# LTE.net
KiCad netlist of a schematic drawn in Altium Designer
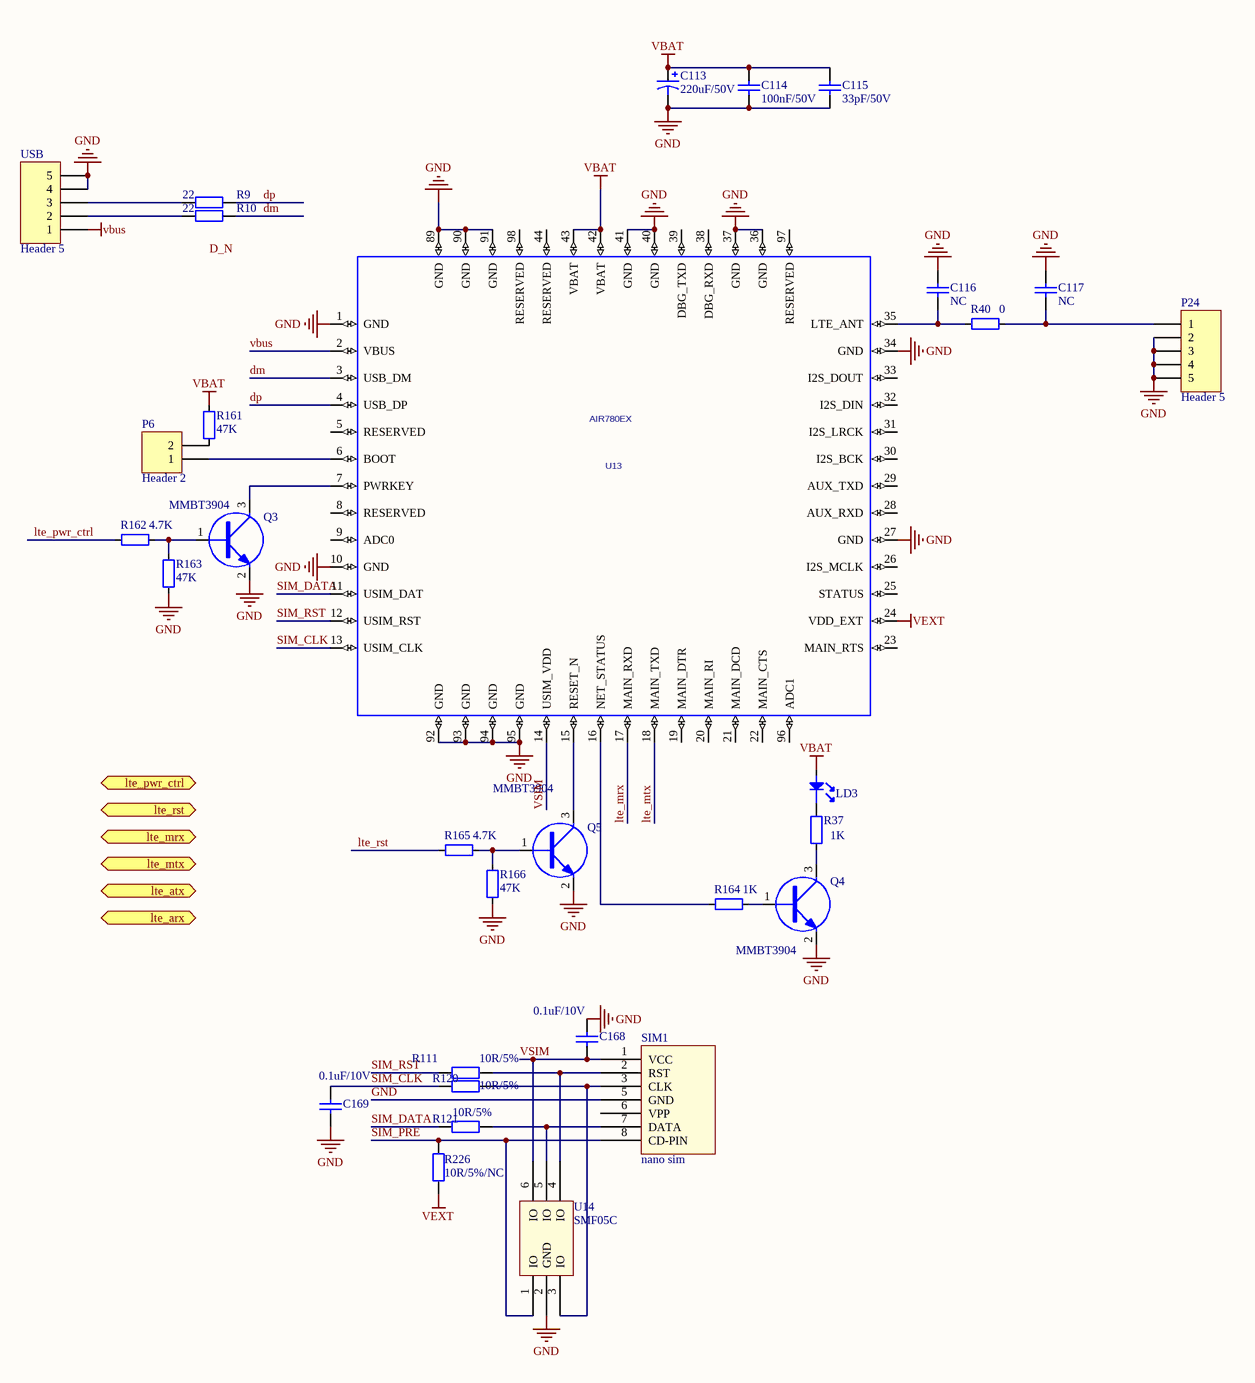
[diagram p0: LTE.SchDoc]

(export (version "E")
  (design (tool "Eeschema 10.0.6"))
  (components
    (comp (ref "C113")
      (value "220uF/50V")
      (footprint "Φ10×10")
      (description "Polarized Capacitor (Radial)")
      (fields (field (name "PUBLISHER") "Altium Limited"))
      (libsource (lib "Miscellaneous Devices") (part "Cap Pol1"))
    )
    (comp (ref "C114")
      (value "100nF/50V")
      (footprint "0603C")
      (description "Capacitor")
      (fields (field (name "PUBLISHER") "Altium Limited"))
      (libsource (lib "Miscellaneous Devices") (part "Cap"))
    )
    (comp (ref "C115")
      (value "33pF/50V")
      (footprint "0603C")
      (description "Capacitor")
      (fields (field (name "PUBLISHER") "Altium Limited"))
      (libsource (lib "Miscellaneous Devices") (part "Cap"))
    )
    (comp (ref "C116")
      (value "NC")
      (footprint "0603c")
      (description "Capacitor")
      (fields (field (name "PUBLISHER") "Altium Limited"))
      (libsource (lib "Miscellaneous Devices") (part "Cap"))
    )
    (comp (ref "C117")
      (value "NC")
      (footprint "0603c")
      (description "Capacitor")
      (fields (field (name "PUBLISHER") "Altium Limited"))
      (libsource (lib "Miscellaneous Devices") (part "Cap"))
    )
    (comp (ref "C168")
      (value "0.1uF/10V")
      (footprint "0603c")
      (description "Capacitor")
      (fields (field (name "PUBLISHER") "Altium Limited"))
      (libsource (lib "Miscellaneous Devices") (part "Cap"))
    )
    (comp (ref "C169")
      (value "0.1uF/10V")
      (footprint "0603c")
      (description "Capacitor")
      (fields (field (name "PUBLISHER") "Altium Limited"))
      (libsource (lib "Miscellaneous Devices") (part "Cap"))
    )
    (comp (ref "LD3")
      (value "LED_Green_19-217")
      (footprint "0603led")
      (libsource (lib "RC_M_D_00") (part "LED_Green_19-217"))
    )
    (comp (ref "P6")
      (value "Header 2")
      (footprint "HDR1X2")
      (description "Header, 2-Pin")
      (fields (field (name "PUBLISHER") "Altium Limited"))
      (libsource (lib "Miscellaneous Connectors") (part "Header 2"))
    )
    (comp (ref "P24")
      (value "Header 5")
      (footprint "KH-SMA-KE-Z")
      (description "Header, 5-Pin")
      (fields (field (name "PUBLISHER") "Altium Limited"))
      (libsource (lib "Miscellaneous Connectors") (part "Header 5"))
    )
    (comp (ref "Q3")
      (value "MMBT3904")
      (footprint "SOT23-3")
      (libsource (lib "CenLib") (part "NPN_MMBT3904"))
    )
    (comp (ref "Q4")
      (value "MMBT3904")
      (footprint "SOT23-3")
      (libsource (lib "CenLib") (part "NPN_MMBT3904"))
    )
    (comp (ref "Q5")
      (value "MMBT3904")
      (footprint "SOT23-3")
      (libsource (lib "CenLib") (part "NPN_MMBT3904"))
    )
    (comp (ref "R9")
      (value "22")
      (footprint "0402R")
      (description "Resistor SMD - IEC symbol version")
      (libsource (lib "SX1276_e266v02a") (part "Resistor"))
    )
    (comp (ref "R10")
      (value "22")
      (footprint "0402R")
      (description "Resistor SMD - IEC symbol version")
      (libsource (lib "SX1276_e266v02a") (part "Resistor"))
    )
    (comp (ref "R37") (value "1K") (footprint "0603R") (libsource (lib "RC_M_D_00") (part "RES0603")))
    (comp (ref "R40") (value "0") (footprint "0603r") (libsource (lib "RC_M_D_00") (part "RES0603")))
    (comp (ref "R111")
      (value "10R/5%")
      (footprint "0603r")
      (description "Resistor")
      (fields (field (name "PUBLISHER") "Altium Limited"))
      (libsource (lib "") (part "Res2_1"))
    )
    (comp (ref "R120")
      (value "10R/5%")
      (footprint "0603r")
      (description "Resistor")
      (fields (field (name "PUBLISHER") "Altium Limited"))
      (libsource (lib "") (part "Res2_1"))
    )
    (comp (ref "R121")
      (value "10R/5%")
      (footprint "0603r")
      (description "Resistor")
      (fields (field (name "PUBLISHER") "Altium Limited"))
      (libsource (lib "") (part "Res2_1"))
    )
    (comp (ref "R161") (value "47K") (footprint "0603r") (libsource (lib "RC_M_D_00") (part "RES0603")))
    (comp (ref "R162") (value "4.7K") (footprint "0603R") (libsource (lib "RC_M_D_00") (part "RES0603")))
    (comp (ref "R163") (value "47K") (footprint "0603r") (libsource (lib "RC_M_D_00") (part "RES0603")))
    (comp (ref "R164") (value "1K") (footprint "0603r") (libsource (lib "RC_M_D_00") (part "RES0603")))
    (comp (ref "R165") (value "4.7K") (footprint "0603R") (libsource (lib "RC_M_D_00") (part "RES0603")))
    (comp (ref "R166") (value "47K") (footprint "0603r") (libsource (lib "RC_M_D_00") (part "RES0603")))
    (comp (ref "R226")
      (value "10R/5%/NC")
      (footprint "0603r")
      (description "Resistor")
      (fields (field (name "PUBLISHER") "Altium Limited"))
      (libsource (lib "Miscellaneous Devices") (part "Res2"))
    )
    (comp (ref "SIM1") (value "nano sim") (footprint "Nano SIM") (libsource (lib "lm") (part "nano sim")))
    (comp (ref "U13")
      (value "AIR780EX")
      (footprint "Air780EX_AD:AIR780EX")
      (libsource (lib "*") (part "AIR780EX"))
    )
    (comp (ref "U14") (value "SMF05C") (footprint "sc70-6l") (libsource (lib "lm") (part "SMF05C")))
    (comp (ref "USB")
      (value "Header 5")
      (footprint "USB-MICRO-5P")
      (description "Header, 5-Pin")
      (fields (field (name "PUBLISHER") "Altium Limited"))
      (libsource (lib "") (part "Header 5_1"))
    )
  )
  (nets
    (net (code "2") (name "/SIM_CLK") (class "Default")
      (node (ref "C169") (pin "1") (pinfunction "1_1") (pintype "passive"))
      (node (ref "R120") (pin "2") (pinfunction "2_2") (pintype "passive"))
      (node (ref "U13") (pin "13") (pinfunction "USIM_CLK_13") (pintype "bidirectional"))
    )
    (net (code "3") (name "/SIM_DATA") (class "Default")
      (node (ref "R121") (pin "2") (pinfunction "2_2") (pintype "passive"))
      (node (ref "U13") (pin "11") (pinfunction "USIM_DAT_11") (pintype "bidirectional"))
    )
    (net (code "4") (name "/SIM_PRE") (class "Default")
      (node (ref "R226") (pin "1") (pinfunction "1_1") (pintype "passive"))
      (node (ref "SIM1") (pin "8") (pinfunction "CD-PIN_8") (pintype "passive"))
      (node (ref "U14") (pin "1") (pinfunction "IO_1") (pintype "passive"))
    )
    (net (code "5") (name "/SIM_RST") (class "Default")
      (node (ref "R111") (pin "2") (pinfunction "2_2") (pintype "passive"))
      (node (ref "U13") (pin "12") (pinfunction "USIM_RST_12") (pintype "bidirectional"))
    )
    (net (code "6") (name "/VSIM") (class "Default")
      (node (ref "C168") (pin "2") (pinfunction "2_2") (pintype "passive"))
      (node (ref "SIM1") (pin "1") (pinfunction "VCC_1") (pintype "passive"))
      (node (ref "U13") (pin "14") (pinfunction "USIM_VDD_14") (pintype "bidirectional"))
      (node (ref "U14") (pin "6") (pinfunction "IO_6") (pintype "passive"))
    )
    (net (code "7") (name "/dm") (class "Default")
      (node (ref "R10") (pin "2") (pinfunction "2_2") (pintype "passive"))
      (node (ref "U13") (pin "3") (pinfunction "USB_DM_3") (pintype "bidirectional"))
    )
    (net (code "8") (name "/dp") (class "Default")
      (node (ref "R9") (pin "2") (pinfunction "2_2") (pintype "passive"))
      (node (ref "U13") (pin "4") (pinfunction "USB_DP_4") (pintype "bidirectional"))
    )
    (net (code "11") (name "/lte_mrx") (class "Default")
      (node (ref "U13") (pin "17") (pinfunction "MAIN_RXD_17") (pintype "bidirectional"))
    )
    (net (code "12") (name "/lte_mtx") (class "Default")
      (node (ref "U13") (pin "18") (pinfunction "MAIN_TXD_18") (pintype "bidirectional"))
    )
    (net (code "13") (name "/lte_pwr_ctrl") (class "Default")
      (node (ref "R162") (pin "1") (pinfunction "1_1") (pintype "passive"))
    )
    (net (code "14") (name "/lte_rst") (class "Default")
      (node (ref "R165") (pin "1") (pinfunction "1_1") (pintype "passive"))
    )
    (net (code "15") (name "GND") (class "Default")
      (node (ref "C113") (pin "2") (pinfunction "2_2") (pintype "passive"))
      (node (ref "C114") (pin "1") (pinfunction "1_1") (pintype "passive"))
      (node (ref "C115") (pin "1") (pinfunction "1_1") (pintype "passive"))
      (node (ref "C116") (pin "2") (pinfunction "2_2") (pintype "passive"))
      (node (ref "C117") (pin "2") (pinfunction "2_2") (pintype "passive"))
      (node (ref "C168") (pin "1") (pinfunction "1_1") (pintype "passive"))
      (node (ref "C169") (pin "2") (pinfunction "2_2") (pintype "passive"))
      (node (ref "P24") (pin "2") (pinfunction "2_2") (pintype "passive"))
      (node (ref "P24") (pin "3") (pinfunction "3_3") (pintype "passive"))
      (node (ref "P24") (pin "4") (pinfunction "4_4") (pintype "passive"))
      (node (ref "P24") (pin "5") (pinfunction "5_5") (pintype "passive"))
      (node (ref "Q3") (pin "2") (pinfunction "E_2") (pintype "passive"))
      (node (ref "Q4") (pin "2") (pinfunction "E_2") (pintype "passive"))
      (node (ref "Q5") (pin "2") (pinfunction "E_2") (pintype "passive"))
      (node (ref "R163") (pin "1") (pinfunction "1_1") (pintype "passive"))
      (node (ref "R166") (pin "1") (pinfunction "1_1") (pintype "passive"))
      (node (ref "SIM1") (pin "5") (pinfunction "GND_5") (pintype "passive"))
      (node (ref "U13") (pin "1") (pinfunction "GND_1") (pintype "bidirectional"))
      (node (ref "U13") (pin "10") (pinfunction "GND_10") (pintype "bidirectional"))
      (node (ref "U13") (pin "27") (pinfunction "GND_27") (pintype "bidirectional"))
      (node (ref "U13") (pin "34") (pinfunction "GND_34") (pintype "bidirectional"))
      (node (ref "U13") (pin "36") (pinfunction "GND_36") (pintype "bidirectional"))
      (node (ref "U13") (pin "37") (pinfunction "GND_37") (pintype "bidirectional"))
      (node (ref "U13") (pin "40") (pinfunction "GND_40") (pintype "bidirectional"))
      (node (ref "U13") (pin "41") (pinfunction "GND_41") (pintype "bidirectional"))
      (node (ref "U13") (pin "89") (pinfunction "GND_89") (pintype "bidirectional"))
      (node (ref "U13") (pin "90") (pinfunction "GND_90") (pintype "bidirectional"))
      (node (ref "U13") (pin "91") (pinfunction "GND_91") (pintype "bidirectional"))
      (node (ref "U13") (pin "92") (pinfunction "GND_92") (pintype "bidirectional"))
      (node (ref "U13") (pin "93") (pinfunction "GND_93") (pintype "bidirectional"))
      (node (ref "U13") (pin "94") (pinfunction "GND_94") (pintype "bidirectional"))
      (node (ref "U13") (pin "95") (pinfunction "GND_95") (pintype "bidirectional"))
      (node (ref "U14") (pin "2") (pinfunction "GND_2") (pintype "passive"))
      (node (ref "USB") (pin "4") (pinfunction "4_4") (pintype "passive"))
      (node (ref "USB") (pin "5") (pinfunction "5_5") (pintype "passive"))
    )
    (net (code "16") (name "Net-(C117-Pad1)") (class "Default")
      (node (ref "C117") (pin "1") (pinfunction "1_1") (pintype "passive"))
      (node (ref "P24") (pin "1") (pinfunction "1_1") (pintype "passive"))
      (node (ref "R40") (pin "2") (pinfunction "2_2") (pintype "passive"))
    )
    (net (code "17") (name "Net-(LD3-Pad2)") (class "Default")
      (node (ref "LD3") (pin "2") (pinfunction "2_2") (pintype "passive"))
      (node (ref "R37") (pin "1") (pinfunction "1_1") (pintype "passive"))
    )
    (net (code "18") (name "Net-(P6-Pad2)") (class "Default")
      (node (ref "P6") (pin "2") (pinfunction "2_2") (pintype "passive"))
      (node (ref "R161") (pin "1") (pinfunction "1_1") (pintype "passive"))
    )
    (net (code "19") (name "Net-(Q3-B)") (class "Default")
      (node (ref "Q3") (pin "1") (pinfunction "B_1") (pintype "passive"))
      (node (ref "R162") (pin "2") (pinfunction "2_2") (pintype "passive"))
      (node (ref "R163") (pin "2") (pinfunction "2_2") (pintype "passive"))
    )
    (net (code "20") (name "Net-(Q3-C)") (class "Default")
      (node (ref "Q3") (pin "3") (pinfunction "C_3") (pintype "passive"))
      (node (ref "U13") (pin "7") (pinfunction "PWRKEY_7") (pintype "bidirectional"))
    )
    (net (code "21") (name "Net-(Q4-B)") (class "Default")
      (node (ref "Q4") (pin "1") (pinfunction "B_1") (pintype "passive"))
      (node (ref "R164") (pin "2") (pinfunction "2_2") (pintype "passive"))
    )
    (net (code "22") (name "Net-(Q4-C)") (class "Default")
      (node (ref "Q4") (pin "3") (pinfunction "C_3") (pintype "passive"))
      (node (ref "R37") (pin "2") (pinfunction "2_2") (pintype "passive"))
    )
    (net (code "23") (name "Net-(Q5-B)") (class "Default")
      (node (ref "Q5") (pin "1") (pinfunction "B_1") (pintype "passive"))
      (node (ref "R165") (pin "2") (pinfunction "2_2") (pintype "passive"))
      (node (ref "R166") (pin "2") (pinfunction "2_2") (pintype "passive"))
    )
    (net (code "24") (name "Net-(Q5-C)") (class "Default")
      (node (ref "Q5") (pin "3") (pinfunction "C_3") (pintype "passive"))
      (node (ref "U13") (pin "15") (pinfunction "RESET_N_15") (pintype "bidirectional"))
    )
    (net (code "25") (name "Net-(R9-Pad1)") (class "Default")
      (node (ref "R9") (pin "1") (pinfunction "1_1") (pintype "passive"))
      (node (ref "USB") (pin "3") (pinfunction "3_3") (pintype "passive"))
    )
    (net (code "26") (name "Net-(R10-Pad1)") (class "Default")
      (node (ref "R10") (pin "1") (pinfunction "1_1") (pintype "passive"))
      (node (ref "USB") (pin "2") (pinfunction "2_2") (pintype "passive"))
    )
    (net (code "27") (name "Net-(SIM1-CLK)") (class "Default")
      (node (ref "R120") (pin "1") (pinfunction "1_1") (pintype "passive"))
      (node (ref "SIM1") (pin "3") (pinfunction "CLK_3") (pintype "passive"))
      (node (ref "U14") (pin "3") (pinfunction "IO_3") (pintype "passive"))
    )
    (net (code "28") (name "Net-(SIM1-DATA)") (class "Default")
      (node (ref "R121") (pin "1") (pinfunction "1_1") (pintype "passive"))
      (node (ref "SIM1") (pin "7") (pinfunction "DATA_7") (pintype "passive"))
      (node (ref "U14") (pin "5") (pinfunction "IO_5") (pintype "passive"))
    )
    (net (code "29") (name "Net-(SIM1-RST)") (class "Default")
      (node (ref "R111") (pin "1") (pinfunction "1_1") (pintype "passive"))
      (node (ref "SIM1") (pin "2") (pinfunction "RST_2") (pintype "passive"))
      (node (ref "U14") (pin "4") (pinfunction "IO_4") (pintype "passive"))
    )
    (net (code "30") (name "Net-(U13-BOOT)") (class "Default")
      (node (ref "P6") (pin "1") (pinfunction "1_1") (pintype "passive"))
      (node (ref "U13") (pin "6") (pinfunction "BOOT_6") (pintype "bidirectional"))
    )
    (net (code "31") (name "Net-(U13-LTE_ANT)") (class "Default")
      (node (ref "C116") (pin "1") (pinfunction "1_1") (pintype "passive"))
      (node (ref "R40") (pin "1") (pinfunction "1_1") (pintype "passive"))
      (node (ref "U13") (pin "35") (pinfunction "LTE_ANT_35") (pintype "bidirectional"))
    )
    (net (code "32") (name "Net-(U13-NET_STATUS)") (class "Default")
      (node (ref "R164") (pin "1") (pinfunction "1_1") (pintype "passive"))
      (node (ref "U13") (pin "16") (pinfunction "NET_STATUS_16") (pintype "bidirectional"))
    )
    (net (code "33") (name "VBAT") (class "Default")
      (node (ref "C113") (pin "1") (pinfunction "1_1") (pintype "passive"))
      (node (ref "C114") (pin "2") (pinfunction "2_2") (pintype "passive"))
      (node (ref "C115") (pin "2") (pinfunction "2_2") (pintype "passive"))
      (node (ref "LD3") (pin "1") (pinfunction "1_1") (pintype "passive"))
      (node (ref "R161") (pin "2") (pinfunction "2_2") (pintype "passive"))
      (node (ref "U13") (pin "42") (pinfunction "VBAT_42") (pintype "bidirectional"))
      (node (ref "U13") (pin "43") (pinfunction "VBAT_43") (pintype "bidirectional"))
    )
    (net (code "34") (name "VEXT") (class "Default")
      (node (ref "R226") (pin "2") (pinfunction "2_2") (pintype "passive"))
      (node (ref "U13") (pin "24") (pinfunction "VDD_EXT_24") (pintype "bidirectional"))
    )
    (net (code "35") (name "unconnected-(SIM1-VPP-Pad6)") (class "Default")
      (node (ref "SIM1") (pin "6") (pinfunction "VPP_6") (pintype "passive"))
    )
    (net (code "36") (name "unconnected-(U13-ADC0-Pad9)") (class "Default")
      (node (ref "U13") (pin "9") (pinfunction "ADC0_9") (pintype "bidirectional"))
    )
    (net (code "37") (name "unconnected-(U13-ADC1-Pad96)") (class "Default")
      (node (ref "U13") (pin "96") (pinfunction "ADC1_96") (pintype "bidirectional"))
    )
    (net (code "38") (name "unconnected-(U13-AUX_RXD-Pad28)") (class "Default")
      (node (ref "U13") (pin "28") (pinfunction "AUX_RXD_28") (pintype "bidirectional"))
    )
    (net (code "39") (name "unconnected-(U13-AUX_TXD-Pad29)") (class "Default")
      (node (ref "U13") (pin "29") (pinfunction "AUX_TXD_29") (pintype "bidirectional"))
    )
    (net (code "40") (name "unconnected-(U13-DBG_RXD-Pad38)") (class "Default")
      (node (ref "U13") (pin "38") (pinfunction "DBG_RXD_38") (pintype "bidirectional"))
    )
    (net (code "41") (name "unconnected-(U13-DBG_TXD-Pad39)") (class "Default")
      (node (ref "U13") (pin "39") (pinfunction "DBG_TXD_39") (pintype "bidirectional"))
    )
    (net (code "42") (name "unconnected-(U13-I2S_BCK-Pad30)") (class "Default")
      (node (ref "U13") (pin "30") (pinfunction "I2S_BCK_30") (pintype "bidirectional"))
    )
    (net (code "43") (name "unconnected-(U13-I2S_DIN-Pad32)") (class "Default")
      (node (ref "U13") (pin "32") (pinfunction "I2S_DIN_32") (pintype "bidirectional"))
    )
    (net (code "44") (name "unconnected-(U13-I2S_DOUT-Pad33)") (class "Default")
      (node (ref "U13") (pin "33") (pinfunction "I2S_DOUT_33") (pintype "bidirectional"))
    )
    (net (code "45") (name "unconnected-(U13-I2S_LRCK-Pad31)") (class "Default")
      (node (ref "U13") (pin "31") (pinfunction "I2S_LRCK_31") (pintype "bidirectional"))
    )
    (net (code "46") (name "unconnected-(U13-I2S_MCLK-Pad26)") (class "Default")
      (node (ref "U13") (pin "26") (pinfunction "I2S_MCLK_26") (pintype "bidirectional"))
    )
    (net (code "47") (name "unconnected-(U13-MAIN_CTS-Pad22)") (class "Default")
      (node (ref "U13") (pin "22") (pinfunction "MAIN_CTS_22") (pintype "bidirectional"))
    )
    (net (code "48") (name "unconnected-(U13-MAIN_DCD-Pad21)") (class "Default")
      (node (ref "U13") (pin "21") (pinfunction "MAIN_DCD_21") (pintype "bidirectional"))
    )
    (net (code "49") (name "unconnected-(U13-MAIN_DTR-Pad19)") (class "Default")
      (node (ref "U13") (pin "19") (pinfunction "MAIN_DTR_19") (pintype "bidirectional"))
    )
    (net (code "50") (name "unconnected-(U13-MAIN_RI-Pad20)") (class "Default")
      (node (ref "U13") (pin "20") (pinfunction "MAIN_RI_20") (pintype "bidirectional"))
    )
    (net (code "51") (name "unconnected-(U13-MAIN_RTS-Pad23)") (class "Default")
      (node (ref "U13") (pin "23") (pinfunction "MAIN_RTS_23") (pintype "bidirectional"))
    )
    (net (code "52") (name "unconnected-(U13-RESERVED-Pad5)") (class "Default")
      (node (ref "U13") (pin "5") (pinfunction "RESERVED_5") (pintype "bidirectional"))
    )
    (net (code "53") (name "unconnected-(U13-RESERVED-Pad8)") (class "Default")
      (node (ref "U13") (pin "8") (pinfunction "RESERVED_8") (pintype "bidirectional"))
    )
    (net (code "54") (name "unconnected-(U13-RESERVED-Pad44)") (class "Default")
      (node (ref "U13") (pin "44") (pinfunction "RESERVED_44") (pintype "bidirectional"))
    )
    (net (code "55") (name "unconnected-(U13-RESERVED-Pad97)") (class "Default")
      (node (ref "U13") (pin "97") (pinfunction "RESERVED_97") (pintype "bidirectional"))
    )
    (net (code "56") (name "unconnected-(U13-RESERVED-Pad98)") (class "Default")
      (node (ref "U13") (pin "98") (pinfunction "RESERVED_98") (pintype "bidirectional"))
    )
    (net (code "57") (name "unconnected-(U13-STATUS-Pad25)") (class "Default")
      (node (ref "U13") (pin "25") (pinfunction "STATUS_25") (pintype "bidirectional"))
    )
    (net (code "58") (name "vbus") (class "Default")
      (node (ref "U13") (pin "2") (pinfunction "VBUS_2") (pintype "bidirectional"))
      (node (ref "USB") (pin "1") (pinfunction "1_1") (pintype "passive"))
    )
  )
)
